# 8V54816A_SUPPLY.net
KiCad netlist of a schematic drawn in Altium Designer
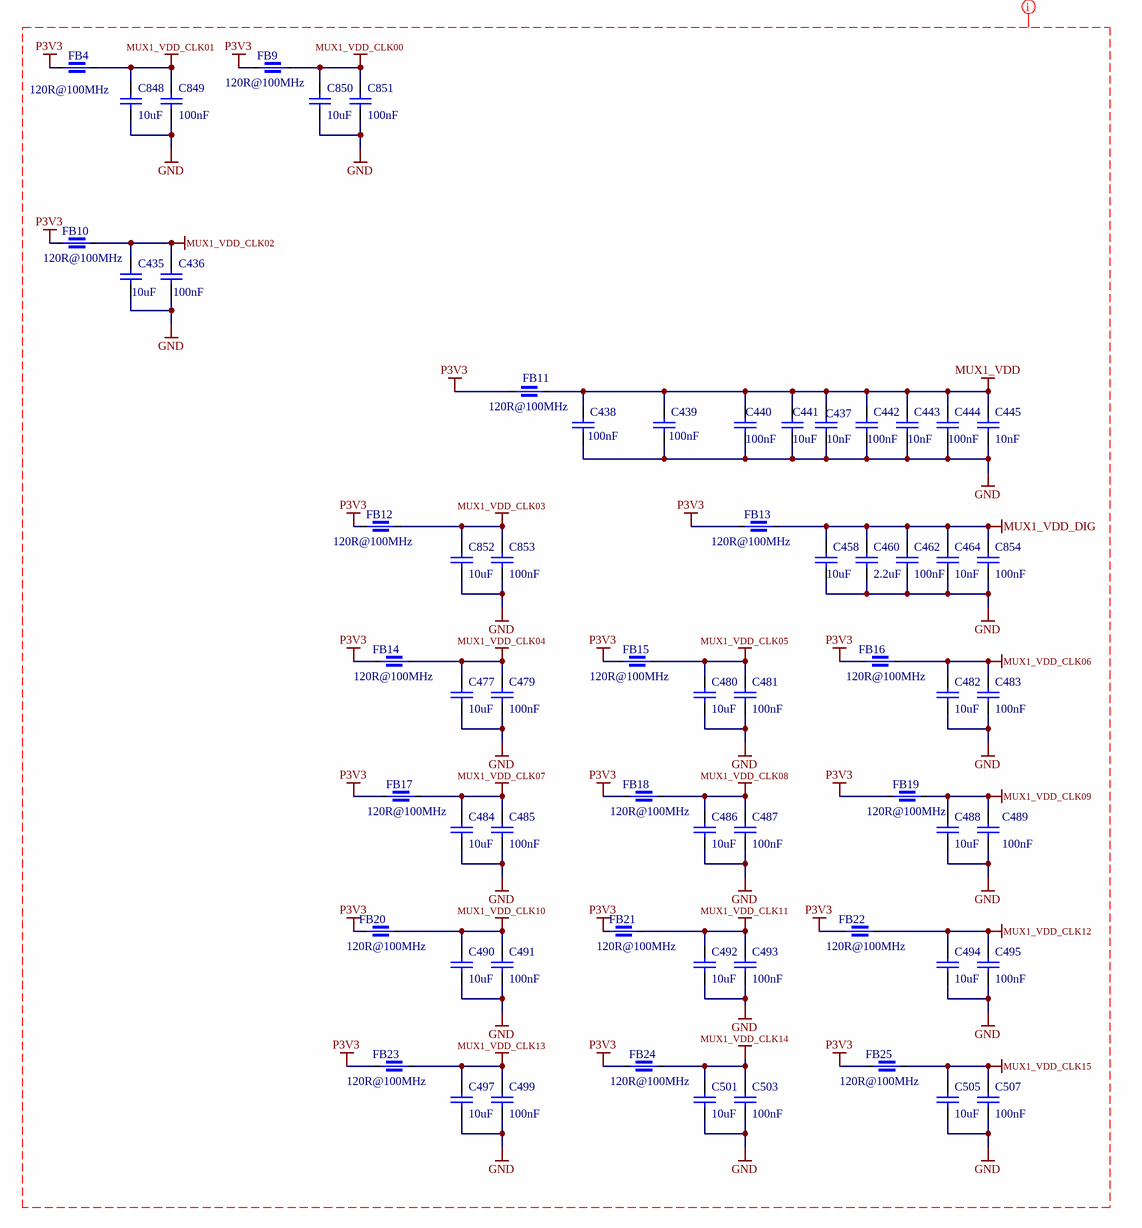
[diagram p0: 8V54816A_SUPPLY.SchDoc]

(export (version "E")
  (design (tool "Eeschema 10.0.6"))
  (components
    (comp (ref "C435")
      (value "10uF")
      (footprint "CAPC1608X87N")
      (description "Non-polarised capacitor")
      (fields
        (field (name "MANUFACTURER PART NUMBER") "CC0603_10uF_6.3V_20%_X5R")
        (field (name "MANUFACTURER") "GENERIC")
        (field (name "AUTHOR") "CERN DEM JLC")
      )
      (libsource (lib "Capacitors") (part "Capacitor - non polarized"))
    )
    (comp (ref "C436")
      (value "100nF")
      (footprint "CAPC0603X33N")
      (description "Non-polarised capacitor")
      (fields
        (field (name "MANUFACTURER PART NUMBER") "CC0201_100NF_6.3V_10%_X5R")
        (field (name "MANUFACTURER") "GENERIC")
        (field (name "AUTHOR") "CERN DEM JLC")
      )
      (libsource (lib "Capacitors") (part "Capacitor - non polarized"))
    )
    (comp (ref "C437")
      (value "10nF")
      (footprint "CAPC0603X33N")
      (description "Non-polarised capacitor")
      (fields
        (field (name "MANUFACTURER PART NUMBER") "CC0201_10NF_10V_10%_X5R")
        (field (name "MANUFACTURER") "GENERIC")
        (field (name "AUTHOR") "CERN DEM JLC")
      )
      (libsource (lib "Capacitors") (part "Capacitor - non polarized"))
    )
    (comp (ref "C438")
      (value "100nF")
      (footprint "CAPC0603X33N")
      (description "Non-polarised capacitor")
      (fields
        (field (name "MANUFACTURER PART NUMBER") "CC0201_100NF_6.3V_10%_X5R")
        (field (name "MANUFACTURER") "GENERIC")
        (field (name "AUTHOR") "CERN DEM JLC")
      )
      (libsource (lib "Capacitors") (part "Capacitor - non polarized"))
    )
    (comp (ref "C439")
      (value "100nF")
      (footprint "CAPC0603X33N")
      (description "Non-polarised capacitor")
      (fields
        (field (name "MANUFACTURER PART NUMBER") "CC0201_100NF_6.3V_10%_X5R")
        (field (name "MANUFACTURER") "GENERIC")
        (field (name "AUTHOR") "CERN DEM JLC")
      )
      (libsource (lib "Capacitors") (part "Capacitor - non polarized"))
    )
    (comp (ref "C440")
      (value "100nF")
      (footprint "CAPC0603X33N")
      (description "Non-polarised capacitor")
      (fields
        (field (name "MANUFACTURER PART NUMBER") "CC0201_100NF_6.3V_10%_X5R")
        (field (name "MANUFACTURER") "GENERIC")
        (field (name "AUTHOR") "CERN DEM JLC")
      )
      (libsource (lib "Capacitors") (part "Capacitor - non polarized"))
    )
    (comp (ref "C441")
      (value "10uF")
      (footprint "CAPC1608X87N")
      (description "Non-polarised capacitor")
      (fields
        (field (name "MANUFACTURER PART NUMBER") "CC0603_10uF_6.3V_20%_X5R")
        (field (name "MANUFACTURER") "GENERIC")
        (field (name "AUTHOR") "CERN DEM JLC")
      )
      (libsource (lib "Capacitors") (part "Capacitor - non polarized"))
    )
    (comp (ref "C442")
      (value "100nF")
      (footprint "CAPC0603X33N")
      (description "Non-polarised capacitor")
      (fields
        (field (name "MANUFACTURER PART NUMBER") "CC0201_100NF_6.3V_10%_X5R")
        (field (name "MANUFACTURER") "GENERIC")
        (field (name "AUTHOR") "CERN DEM JLC")
      )
      (libsource (lib "Capacitors") (part "Capacitor - non polarized"))
    )
    (comp (ref "C443")
      (value "10nF")
      (footprint "CAPC0603X33N")
      (description "Non-polarised capacitor")
      (fields
        (field (name "MANUFACTURER PART NUMBER") "CC0201_10NF_10V_10%_X5R")
        (field (name "MANUFACTURER") "GENERIC")
        (field (name "AUTHOR") "CERN DEM JLC")
      )
      (libsource (lib "Capacitors") (part "Capacitor - non polarized"))
    )
    (comp (ref "C444")
      (value "100nF")
      (footprint "CAPC0603X33N")
      (description "Non-polarised capacitor")
      (fields
        (field (name "MANUFACTURER PART NUMBER") "CC0201_100NF_6.3V_10%_X5R")
        (field (name "MANUFACTURER") "GENERIC")
        (field (name "AUTHOR") "CERN DEM JLC")
      )
      (libsource (lib "Capacitors") (part "Capacitor - non polarized"))
    )
    (comp (ref "C445")
      (value "10nF")
      (footprint "CAPC0603X33N")
      (description "Non-polarised capacitor")
      (fields
        (field (name "MANUFACTURER PART NUMBER") "CC0201_10NF_10V_10%_X5R")
        (field (name "MANUFACTURER") "GENERIC")
        (field (name "AUTHOR") "CERN DEM JLC")
      )
      (libsource (lib "Capacitors") (part "Capacitor - non polarized"))
    )
    (comp (ref "C458")
      (value "10uF")
      (footprint "CAPC1608X87N")
      (description "Non-polarised capacitor")
      (fields
        (field (name "MANUFACTURER PART NUMBER") "CC0603_10uF_6.3V_20%_X5R")
        (field (name "MANUFACTURER") "GENERIC")
        (field (name "AUTHOR") "CERN DEM JLC")
      )
      (libsource (lib "Capacitors") (part "Capacitor - non polarized"))
    )
    (comp (ref "C460")
      (value "2.2uF")
      (footprint "CAPC1005X55N")
      (description "Non-polarised capacitor")
      (fields
        (field (name "MANUFACTURER PART NUMBER") "CC0402_2.2UF_6.3V_10%_X5R")
        (field (name "MANUFACTURER") "GENERIC")
        (field (name "AUTHOR") "CERN DEM JMW")
      )
      (libsource (lib "Capacitors") (part "Capacitor - non polarized"))
    )
    (comp (ref "C462")
      (value "100nF")
      (footprint "CAPC0603X33N")
      (description "Non-polarised capacitor")
      (fields
        (field (name "MANUFACTURER PART NUMBER") "CC0201_100NF_6.3V_10%_X5R")
        (field (name "MANUFACTURER") "GENERIC")
        (field (name "AUTHOR") "CERN DEM JLC")
      )
      (libsource (lib "Capacitors") (part "Capacitor - non polarized"))
    )
    (comp (ref "C464")
      (value "10nF")
      (footprint "CAPC0603X33N")
      (description "Non-polarised capacitor")
      (fields
        (field (name "MANUFACTURER PART NUMBER") "CC0201_10NF_10V_10%_X5R")
        (field (name "MANUFACTURER") "GENERIC")
        (field (name "AUTHOR") "CERN DEM JLC")
      )
      (libsource (lib "Capacitors") (part "Capacitor - non polarized"))
    )
    (comp (ref "C477")
      (value "10uF")
      (footprint "CAPC1608X87N")
      (description "Non-polarised capacitor")
      (fields
        (field (name "MANUFACTURER PART NUMBER") "CC0603_10uF_6.3V_20%_X5R")
        (field (name "MANUFACTURER") "GENERIC")
        (field (name "AUTHOR") "CERN DEM JLC")
      )
      (libsource (lib "Capacitors") (part "Capacitor - non polarized"))
    )
    (comp (ref "C479")
      (value "100nF")
      (footprint "CAPC0603X33N")
      (description "Non-polarised capacitor")
      (fields
        (field (name "MANUFACTURER PART NUMBER") "CC0201_100NF_6.3V_10%_X5R")
        (field (name "MANUFACTURER") "GENERIC")
        (field (name "AUTHOR") "CERN DEM JLC")
      )
      (libsource (lib "Capacitors") (part "Capacitor - non polarized"))
    )
    (comp (ref "C480")
      (value "10uF")
      (footprint "CAPC1608X87N")
      (description "Non-polarised capacitor")
      (fields
        (field (name "MANUFACTURER PART NUMBER") "CC0603_10uF_6.3V_20%_X5R")
        (field (name "MANUFACTURER") "GENERIC")
        (field (name "AUTHOR") "CERN DEM JLC")
      )
      (libsource (lib "Capacitors") (part "Capacitor - non polarized"))
    )
    (comp (ref "C481")
      (value "100nF")
      (footprint "CAPC0603X33N")
      (description "Non-polarised capacitor")
      (fields
        (field (name "MANUFACTURER PART NUMBER") "CC0201_100NF_6.3V_10%_X5R")
        (field (name "MANUFACTURER") "GENERIC")
        (field (name "AUTHOR") "CERN DEM JLC")
      )
      (libsource (lib "Capacitors") (part "Capacitor - non polarized"))
    )
    (comp (ref "C482")
      (value "10uF")
      (footprint "CAPC1608X87N")
      (description "Non-polarised capacitor")
      (fields
        (field (name "MANUFACTURER PART NUMBER") "CC0603_10uF_6.3V_20%_X5R")
        (field (name "MANUFACTURER") "GENERIC")
        (field (name "AUTHOR") "CERN DEM JLC")
      )
      (libsource (lib "Capacitors") (part "Capacitor - non polarized"))
    )
    (comp (ref "C483")
      (value "100nF")
      (footprint "CAPC0603X33N")
      (description "Non-polarised capacitor")
      (fields
        (field (name "MANUFACTURER PART NUMBER") "CC0201_100NF_6.3V_10%_X5R")
        (field (name "MANUFACTURER") "GENERIC")
        (field (name "AUTHOR") "CERN DEM JLC")
      )
      (libsource (lib "Capacitors") (part "Capacitor - non polarized"))
    )
    (comp (ref "C484")
      (value "10uF")
      (footprint "CAPC1608X87N")
      (description "Non-polarised capacitor")
      (fields
        (field (name "MANUFACTURER PART NUMBER") "CC0603_10uF_6.3V_20%_X5R")
        (field (name "MANUFACTURER") "GENERIC")
        (field (name "AUTHOR") "CERN DEM JLC")
      )
      (libsource (lib "Capacitors") (part "Capacitor - non polarized"))
    )
    (comp (ref "C485")
      (value "100nF")
      (footprint "CAPC0603X33N")
      (description "Non-polarised capacitor")
      (fields
        (field (name "MANUFACTURER PART NUMBER") "CC0201_100NF_6.3V_10%_X5R")
        (field (name "MANUFACTURER") "GENERIC")
        (field (name "AUTHOR") "CERN DEM JLC")
      )
      (libsource (lib "Capacitors") (part "Capacitor - non polarized"))
    )
    (comp (ref "C486")
      (value "10uF")
      (footprint "CAPC1608X87N")
      (description "Non-polarised capacitor")
      (fields
        (field (name "MANUFACTURER PART NUMBER") "CC0603_10uF_6.3V_20%_X5R")
        (field (name "MANUFACTURER") "GENERIC")
        (field (name "AUTHOR") "CERN DEM JLC")
      )
      (libsource (lib "Capacitors") (part "Capacitor - non polarized"))
    )
    (comp (ref "C487")
      (value "100nF")
      (footprint "CAPC0603X33N")
      (description "Non-polarised capacitor")
      (fields
        (field (name "MANUFACTURER PART NUMBER") "CC0201_100NF_6.3V_10%_X5R")
        (field (name "MANUFACTURER") "GENERIC")
        (field (name "AUTHOR") "CERN DEM JLC")
      )
      (libsource (lib "Capacitors") (part "Capacitor - non polarized"))
    )
    (comp (ref "C488")
      (value "10uF")
      (footprint "CAPC1608X87N")
      (description "Non-polarised capacitor")
      (fields
        (field (name "MANUFACTURER PART NUMBER") "CC0603_10uF_6.3V_20%_X5R")
        (field (name "MANUFACTURER") "GENERIC")
        (field (name "AUTHOR") "CERN DEM JLC")
      )
      (libsource (lib "Capacitors") (part "Capacitor - non polarized"))
    )
    (comp (ref "C489")
      (value "100nF")
      (footprint "CAPC0603X33N")
      (description "Non-polarised capacitor")
      (fields
        (field (name "MANUFACTURER PART NUMBER") "CC0201_100NF_6.3V_10%_X5R")
        (field (name "MANUFACTURER") "GENERIC")
        (field (name "AUTHOR") "CERN DEM JLC")
      )
      (libsource (lib "Capacitors") (part "Capacitor - non polarized"))
    )
    (comp (ref "C490")
      (value "10uF")
      (footprint "CAPC1608X87N")
      (description "Non-polarised capacitor")
      (fields
        (field (name "MANUFACTURER PART NUMBER") "CC0603_10uF_6.3V_20%_X5R")
        (field (name "MANUFACTURER") "GENERIC")
        (field (name "AUTHOR") "CERN DEM JLC")
      )
      (libsource (lib "Capacitors") (part "Capacitor - non polarized"))
    )
    (comp (ref "C491")
      (value "100nF")
      (footprint "CAPC0603X33N")
      (description "Non-polarised capacitor")
      (fields
        (field (name "MANUFACTURER PART NUMBER") "CC0201_100NF_6.3V_10%_X5R")
        (field (name "MANUFACTURER") "GENERIC")
        (field (name "AUTHOR") "CERN DEM JLC")
      )
      (libsource (lib "Capacitors") (part "Capacitor - non polarized"))
    )
    (comp (ref "C492")
      (value "10uF")
      (footprint "CAPC1608X87N")
      (description "Non-polarised capacitor")
      (fields
        (field (name "MANUFACTURER PART NUMBER") "CC0603_10uF_6.3V_20%_X5R")
        (field (name "MANUFACTURER") "GENERIC")
        (field (name "AUTHOR") "CERN DEM JLC")
      )
      (libsource (lib "Capacitors") (part "Capacitor - non polarized"))
    )
    (comp (ref "C493")
      (value "100nF")
      (footprint "CAPC0603X33N")
      (description "Non-polarised capacitor")
      (fields
        (field (name "MANUFACTURER PART NUMBER") "CC0201_100NF_6.3V_10%_X5R")
        (field (name "MANUFACTURER") "GENERIC")
        (field (name "AUTHOR") "CERN DEM JLC")
      )
      (libsource (lib "Capacitors") (part "Capacitor - non polarized"))
    )
    (comp (ref "C494")
      (value "10uF")
      (footprint "CAPC1608X87N")
      (description "Non-polarised capacitor")
      (fields
        (field (name "MANUFACTURER PART NUMBER") "CC0603_10uF_6.3V_20%_X5R")
        (field (name "MANUFACTURER") "GENERIC")
        (field (name "AUTHOR") "CERN DEM JLC")
      )
      (libsource (lib "Capacitors") (part "Capacitor - non polarized"))
    )
    (comp (ref "C495")
      (value "100nF")
      (footprint "CAPC0603X33N")
      (description "Non-polarised capacitor")
      (fields
        (field (name "MANUFACTURER PART NUMBER") "CC0201_100NF_6.3V_10%_X5R")
        (field (name "MANUFACTURER") "GENERIC")
        (field (name "AUTHOR") "CERN DEM JLC")
      )
      (libsource (lib "Capacitors") (part "Capacitor - non polarized"))
    )
    (comp (ref "C497")
      (value "10uF")
      (footprint "CAPC1608X87N")
      (description "Non-polarised capacitor")
      (fields
        (field (name "MANUFACTURER PART NUMBER") "CC0603_10uF_6.3V_20%_X5R")
        (field (name "MANUFACTURER") "GENERIC")
        (field (name "AUTHOR") "CERN DEM JLC")
      )
      (libsource (lib "Capacitors") (part "Capacitor - non polarized"))
    )
    (comp (ref "C499")
      (value "100nF")
      (footprint "CAPC0603X33N")
      (description "Non-polarised capacitor")
      (fields
        (field (name "MANUFACTURER PART NUMBER") "CC0201_100NF_6.3V_10%_X5R")
        (field (name "MANUFACTURER") "GENERIC")
        (field (name "AUTHOR") "CERN DEM JLC")
      )
      (libsource (lib "Capacitors") (part "Capacitor - non polarized"))
    )
    (comp (ref "C501")
      (value "10uF")
      (footprint "CAPC1608X87N")
      (description "Non-polarised capacitor")
      (fields
        (field (name "MANUFACTURER PART NUMBER") "CC0603_10uF_6.3V_20%_X5R")
        (field (name "MANUFACTURER") "GENERIC")
        (field (name "AUTHOR") "CERN DEM JLC")
      )
      (libsource (lib "Capacitors") (part "Capacitor - non polarized"))
    )
    (comp (ref "C503")
      (value "100nF")
      (footprint "CAPC0603X33N")
      (description "Non-polarised capacitor")
      (fields
        (field (name "MANUFACTURER PART NUMBER") "CC0201_100NF_6.3V_10%_X5R")
        (field (name "MANUFACTURER") "GENERIC")
        (field (name "AUTHOR") "CERN DEM JLC")
      )
      (libsource (lib "Capacitors") (part "Capacitor - non polarized"))
    )
    (comp (ref "C505")
      (value "10uF")
      (footprint "CAPC1608X87N")
      (description "Non-polarised capacitor")
      (fields
        (field (name "MANUFACTURER PART NUMBER") "CC0603_10uF_6.3V_20%_X5R")
        (field (name "MANUFACTURER") "GENERIC")
        (field (name "AUTHOR") "CERN DEM JLC")
      )
      (libsource (lib "Capacitors") (part "Capacitor - non polarized"))
    )
    (comp (ref "C507")
      (value "100nF")
      (footprint "CAPC0603X33N")
      (description "Non-polarised capacitor")
      (fields
        (field (name "MANUFACTURER PART NUMBER") "CC0201_100NF_6.3V_10%_X5R")
        (field (name "MANUFACTURER") "GENERIC")
        (field (name "AUTHOR") "CERN DEM JLC")
      )
      (libsource (lib "Capacitors") (part "Capacitor - non polarized"))
    )
    (comp (ref "C848")
      (value "10uF")
      (footprint "CAPC1608X87N")
      (description "Non-polarised capacitor")
      (fields
        (field (name "MANUFACTURER PART NUMBER") "CC0603_10uF_6.3V_20%_X5R")
        (field (name "MANUFACTURER") "GENERIC")
        (field (name "AUTHOR") "CERN DEM JLC")
      )
      (libsource (lib "Capacitors") (part "Capacitor - non polarized"))
    )
    (comp (ref "C849")
      (value "100nF")
      (footprint "CAPC0603X33N")
      (description "Non-polarised capacitor")
      (fields
        (field (name "MANUFACTURER PART NUMBER") "CC0201_100NF_6.3V_10%_X5R")
        (field (name "MANUFACTURER") "GENERIC")
        (field (name "AUTHOR") "CERN DEM JLC")
      )
      (libsource (lib "Capacitors") (part "Capacitor - non polarized"))
    )
    (comp (ref "C850")
      (value "10uF")
      (footprint "CAPC1608X87N")
      (description "Non-polarised capacitor")
      (fields
        (field (name "MANUFACTURER PART NUMBER") "CC0603_10uF_6.3V_20%_X5R")
        (field (name "MANUFACTURER") "GENERIC")
        (field (name "AUTHOR") "CERN DEM JLC")
      )
      (libsource (lib "Capacitors") (part "Capacitor - non polarized"))
    )
    (comp (ref "C851")
      (value "100nF")
      (footprint "CAPC0603X33N")
      (description "Non-polarised capacitor")
      (fields
        (field (name "MANUFACTURER PART NUMBER") "CC0201_100NF_6.3V_10%_X5R")
        (field (name "MANUFACTURER") "GENERIC")
        (field (name "AUTHOR") "CERN DEM JLC")
      )
      (libsource (lib "Capacitors") (part "Capacitor - non polarized"))
    )
    (comp (ref "C852")
      (value "10uF")
      (footprint "CAPC1608X87N")
      (description "Non-polarised capacitor")
      (fields
        (field (name "MANUFACTURER PART NUMBER") "CC0603_10uF_6.3V_20%_X5R")
        (field (name "MANUFACTURER") "GENERIC")
        (field (name "AUTHOR") "CERN DEM JLC")
      )
      (libsource (lib "Capacitors") (part "Capacitor - non polarized"))
    )
    (comp (ref "C853")
      (value "100nF")
      (footprint "CAPC0603X33N")
      (description "Non-polarised capacitor")
      (fields
        (field (name "MANUFACTURER PART NUMBER") "CC0201_100NF_6.3V_10%_X5R")
        (field (name "MANUFACTURER") "GENERIC")
        (field (name "AUTHOR") "CERN DEM JLC")
      )
      (libsource (lib "Capacitors") (part "Capacitor - non polarized"))
    )
    (comp (ref "C854")
      (value "100nF")
      (footprint "CAPC0603X33N")
      (description "Non-polarised capacitor")
      (fields
        (field (name "MANUFACTURER PART NUMBER") "CC0201_100NF_6.3V_10%_X5R")
        (field (name "MANUFACTURER") "GENERIC")
        (field (name "AUTHOR") "CERN DEM JLC")
      )
      (libsource (lib "Capacitors") (part "Capacitor - non polarized"))
    )
    (comp (ref "FB4")
      (value "120R@100MHz")
      (footprint "INDC1005X55N")
      (fields
        (field (name "MANUFACTURER PART NUMBER") "BLM15PX121SN1D")
        (field (name "MANUFACTURER") "MURATA")
        (field (name "PART NUMBER") "IND0402_MURATA_BLM15PX121SN1D")
        (field (name "AUTHOR") "CERN DEM JMW")
      )
      (libsource (lib "Inductors & Transformers") (part "Ferrite Bead"))
    )
    (comp (ref "FB9")
      (value "120R@100MHz")
      (footprint "INDC1005X55N")
      (fields
        (field (name "MANUFACTURER PART NUMBER") "BLM15PX121SN1D")
        (field (name "MANUFACTURER") "MURATA")
        (field (name "PART NUMBER") "IND0402_MURATA_BLM15PX121SN1D")
        (field (name "AUTHOR") "CERN DEM JMW")
      )
      (libsource (lib "Inductors & Transformers") (part "Ferrite Bead"))
    )
    (comp (ref "FB10")
      (value "120R@100MHz")
      (footprint "INDC1005X55N")
      (fields
        (field (name "MANUFACTURER PART NUMBER") "BLM15PX121SN1D")
        (field (name "MANUFACTURER") "MURATA")
        (field (name "PART NUMBER") "IND0402_MURATA_BLM15PX121SN1D")
        (field (name "AUTHOR") "CERN DEM JMW")
      )
      (libsource (lib "Inductors & Transformers") (part "Ferrite Bead"))
    )
    (comp (ref "FB11")
      (value "120R@100MHz")
      (footprint "INDC1005X55N")
      (fields
        (field (name "MANUFACTURER PART NUMBER") "BLM15PX121SN1D")
        (field (name "MANUFACTURER") "MURATA")
        (field (name "PART NUMBER") "IND0402_MURATA_BLM15PX121SN1D")
        (field (name "AUTHOR") "CERN DEM JMW")
      )
      (libsource (lib "Inductors & Transformers") (part "Ferrite Bead"))
    )
    (comp (ref "FB12")
      (value "120R@100MHz")
      (footprint "INDC1005X55N")
      (fields
        (field (name "MANUFACTURER PART NUMBER") "BLM15PX121SN1D")
        (field (name "MANUFACTURER") "MURATA")
        (field (name "PART NUMBER") "IND0402_MURATA_BLM15PX121SN1D")
        (field (name "AUTHOR") "CERN DEM JMW")
      )
      (libsource (lib "Inductors & Transformers") (part "Ferrite Bead"))
    )
    (comp (ref "FB13")
      (value "120R@100MHz")
      (footprint "INDC1005X55N")
      (fields
        (field (name "MANUFACTURER PART NUMBER") "BLM15PX121SN1D")
        (field (name "MANUFACTURER") "MURATA")
        (field (name "PART NUMBER") "IND0402_MURATA_BLM15PX121SN1D")
        (field (name "AUTHOR") "CERN DEM JMW")
      )
      (libsource (lib "Inductors & Transformers") (part "Ferrite Bead"))
    )
    (comp (ref "FB14")
      (value "120R@100MHz")
      (footprint "INDC1005X55N")
      (fields
        (field (name "MANUFACTURER PART NUMBER") "BLM15PX121SN1D")
        (field (name "MANUFACTURER") "MURATA")
        (field (name "PART NUMBER") "IND0402_MURATA_BLM15PX121SN1D")
        (field (name "AUTHOR") "CERN DEM JMW")
      )
      (libsource (lib "Inductors & Transformers") (part "Ferrite Bead"))
    )
    (comp (ref "FB15")
      (value "120R@100MHz")
      (footprint "INDC1005X55N")
      (fields
        (field (name "MANUFACTURER PART NUMBER") "BLM15PX121SN1D")
        (field (name "MANUFACTURER") "MURATA")
        (field (name "PART NUMBER") "IND0402_MURATA_BLM15PX121SN1D")
        (field (name "AUTHOR") "CERN DEM JMW")
      )
      (libsource (lib "Inductors & Transformers") (part "Ferrite Bead"))
    )
    (comp (ref "FB16")
      (value "120R@100MHz")
      (footprint "INDC1005X55N")
      (fields
        (field (name "MANUFACTURER PART NUMBER") "BLM15PX121SN1D")
        (field (name "MANUFACTURER") "MURATA")
        (field (name "PART NUMBER") "IND0402_MURATA_BLM15PX121SN1D")
        (field (name "AUTHOR") "CERN DEM JMW")
      )
      (libsource (lib "Inductors & Transformers") (part "Ferrite Bead"))
    )
    (comp (ref "FB17")
      (value "120R@100MHz")
      (footprint "INDC1005X55N")
      (fields
        (field (name "MANUFACTURER PART NUMBER") "BLM15PX121SN1D")
        (field (name "MANUFACTURER") "MURATA")
        (field (name "PART NUMBER") "IND0402_MURATA_BLM15PX121SN1D")
        (field (name "AUTHOR") "CERN DEM JMW")
      )
      (libsource (lib "Inductors & Transformers") (part "Ferrite Bead"))
    )
    (comp (ref "FB18")
      (value "120R@100MHz")
      (footprint "INDC1005X55N")
      (fields
        (field (name "MANUFACTURER PART NUMBER") "BLM15PX121SN1D")
        (field (name "MANUFACTURER") "MURATA")
        (field (name "PART NUMBER") "IND0402_MURATA_BLM15PX121SN1D")
        (field (name "AUTHOR") "CERN DEM JMW")
      )
      (libsource (lib "Inductors & Transformers") (part "Ferrite Bead"))
    )
    (comp (ref "FB19")
      (value "120R@100MHz")
      (footprint "INDC1005X55N")
      (fields
        (field (name "MANUFACTURER PART NUMBER") "BLM15PX121SN1D")
        (field (name "MANUFACTURER") "MURATA")
        (field (name "PART NUMBER") "IND0402_MURATA_BLM15PX121SN1D")
        (field (name "AUTHOR") "CERN DEM JMW")
      )
      (libsource (lib "Inductors & Transformers") (part "Ferrite Bead"))
    )
    (comp (ref "FB20")
      (value "120R@100MHz")
      (footprint "INDC1005X55N")
      (fields
        (field (name "MANUFACTURER PART NUMBER") "BLM15PX121SN1D")
        (field (name "MANUFACTURER") "MURATA")
        (field (name "PART NUMBER") "IND0402_MURATA_BLM15PX121SN1D")
        (field (name "AUTHOR") "CERN DEM JMW")
      )
      (libsource (lib "Inductors & Transformers") (part "Ferrite Bead"))
    )
    (comp (ref "FB21")
      (value "120R@100MHz")
      (footprint "INDC1005X55N")
      (fields
        (field (name "MANUFACTURER PART NUMBER") "BLM15PX121SN1D")
        (field (name "MANUFACTURER") "MURATA")
        (field (name "PART NUMBER") "IND0402_MURATA_BLM15PX121SN1D")
        (field (name "AUTHOR") "CERN DEM JMW")
      )
      (libsource (lib "Inductors & Transformers") (part "Ferrite Bead"))
    )
    (comp (ref "FB22")
      (value "120R@100MHz")
      (footprint "INDC1005X55N")
      (fields
        (field (name "MANUFACTURER PART NUMBER") "BLM15PX121SN1D")
        (field (name "MANUFACTURER") "MURATA")
        (field (name "PART NUMBER") "IND0402_MURATA_BLM15PX121SN1D")
        (field (name "AUTHOR") "CERN DEM JMW")
      )
      (libsource (lib "Inductors & Transformers") (part "Ferrite Bead"))
    )
    (comp (ref "FB23")
      (value "120R@100MHz")
      (footprint "INDC1005X55N")
      (fields
        (field (name "MANUFACTURER PART NUMBER") "BLM15PX121SN1D")
        (field (name "MANUFACTURER") "MURATA")
        (field (name "PART NUMBER") "IND0402_MURATA_BLM15PX121SN1D")
        (field (name "AUTHOR") "CERN DEM JMW")
      )
      (libsource (lib "Inductors & Transformers") (part "Ferrite Bead"))
    )
    (comp (ref "FB24")
      (value "120R@100MHz")
      (footprint "INDC1005X55N")
      (fields
        (field (name "MANUFACTURER PART NUMBER") "BLM15PX121SN1D")
        (field (name "MANUFACTURER") "MURATA")
        (field (name "PART NUMBER") "IND0402_MURATA_BLM15PX121SN1D")
        (field (name "AUTHOR") "CERN DEM JMW")
      )
      (libsource (lib "Inductors & Transformers") (part "Ferrite Bead"))
    )
    (comp (ref "FB25")
      (value "120R@100MHz")
      (footprint "INDC1005X55N")
      (fields
        (field (name "MANUFACTURER PART NUMBER") "BLM15PX121SN1D")
        (field (name "MANUFACTURER") "MURATA")
        (field (name "PART NUMBER") "IND0402_MURATA_BLM15PX121SN1D")
        (field (name "AUTHOR") "CERN DEM JMW")
      )
      (libsource (lib "Inductors & Transformers") (part "Ferrite Bead"))
    )
  )
  (nets
    (net (code "1") (name "GND") (class "Default")
      (node (ref "C435") (pin "1") (pinfunction "1_1") (pintype "passive"))
      (node (ref "C436") (pin "1") (pinfunction "1_1") (pintype "passive"))
      (node (ref "C437") (pin "1") (pinfunction "1_1") (pintype "passive"))
      (node (ref "C438") (pin "1") (pinfunction "1_1") (pintype "passive"))
      (node (ref "C439") (pin "1") (pinfunction "1_1") (pintype "passive"))
      (node (ref "C440") (pin "1") (pinfunction "1_1") (pintype "passive"))
      (node (ref "C441") (pin "1") (pinfunction "1_1") (pintype "passive"))
      (node (ref "C442") (pin "1") (pinfunction "1_1") (pintype "passive"))
      (node (ref "C443") (pin "1") (pinfunction "1_1") (pintype "passive"))
      (node (ref "C444") (pin "1") (pinfunction "1_1") (pintype "passive"))
      (node (ref "C445") (pin "1") (pinfunction "1_1") (pintype "passive"))
      (node (ref "C458") (pin "1") (pinfunction "1_1") (pintype "passive"))
      (node (ref "C460") (pin "1") (pinfunction "1_1") (pintype "passive"))
      (node (ref "C462") (pin "1") (pinfunction "1_1") (pintype "passive"))
      (node (ref "C464") (pin "1") (pinfunction "1_1") (pintype "passive"))
      (node (ref "C477") (pin "1") (pinfunction "1_1") (pintype "passive"))
      (node (ref "C479") (pin "1") (pinfunction "1_1") (pintype "passive"))
      (node (ref "C480") (pin "1") (pinfunction "1_1") (pintype "passive"))
      (node (ref "C481") (pin "1") (pinfunction "1_1") (pintype "passive"))
      (node (ref "C482") (pin "1") (pinfunction "1_1") (pintype "passive"))
      (node (ref "C483") (pin "1") (pinfunction "1_1") (pintype "passive"))
      (node (ref "C484") (pin "1") (pinfunction "1_1") (pintype "passive"))
      (node (ref "C485") (pin "1") (pinfunction "1_1") (pintype "passive"))
      (node (ref "C486") (pin "1") (pinfunction "1_1") (pintype "passive"))
      (node (ref "C487") (pin "1") (pinfunction "1_1") (pintype "passive"))
      (node (ref "C488") (pin "1") (pinfunction "1_1") (pintype "passive"))
      (node (ref "C489") (pin "1") (pinfunction "1_1") (pintype "passive"))
      (node (ref "C490") (pin "1") (pinfunction "1_1") (pintype "passive"))
      (node (ref "C491") (pin "1") (pinfunction "1_1") (pintype "passive"))
      (node (ref "C492") (pin "1") (pinfunction "1_1") (pintype "passive"))
      (node (ref "C493") (pin "1") (pinfunction "1_1") (pintype "passive"))
      (node (ref "C494") (pin "1") (pinfunction "1_1") (pintype "passive"))
      (node (ref "C495") (pin "1") (pinfunction "1_1") (pintype "passive"))
      (node (ref "C497") (pin "1") (pinfunction "1_1") (pintype "passive"))
      (node (ref "C499") (pin "1") (pinfunction "1_1") (pintype "passive"))
      (node (ref "C501") (pin "1") (pinfunction "1_1") (pintype "passive"))
      (node (ref "C503") (pin "1") (pinfunction "1_1") (pintype "passive"))
      (node (ref "C505") (pin "1") (pinfunction "1_1") (pintype "passive"))
      (node (ref "C507") (pin "1") (pinfunction "1_1") (pintype "passive"))
      (node (ref "C848") (pin "1") (pinfunction "1_1") (pintype "passive"))
      (node (ref "C849") (pin "1") (pinfunction "1_1") (pintype "passive"))
      (node (ref "C850") (pin "1") (pinfunction "1_1") (pintype "passive"))
      (node (ref "C851") (pin "1") (pinfunction "1_1") (pintype "passive"))
      (node (ref "C852") (pin "1") (pinfunction "1_1") (pintype "passive"))
      (node (ref "C853") (pin "1") (pinfunction "1_1") (pintype "passive"))
      (node (ref "C854") (pin "1") (pinfunction "1_1") (pintype "passive"))
    )
    (net (code "2") (name "MUX1_VDD") (class "Default")
      (node (ref "C437") (pin "2") (pinfunction "2_2") (pintype "passive"))
      (node (ref "C438") (pin "2") (pinfunction "2_2") (pintype "passive"))
      (node (ref "C439") (pin "2") (pinfunction "2_2") (pintype "passive"))
      (node (ref "C440") (pin "2") (pinfunction "2_2") (pintype "passive"))
      (node (ref "C441") (pin "2") (pinfunction "2_2") (pintype "passive"))
      (node (ref "C442") (pin "2") (pinfunction "2_2") (pintype "passive"))
      (node (ref "C443") (pin "2") (pinfunction "2_2") (pintype "passive"))
      (node (ref "C444") (pin "2") (pinfunction "2_2") (pintype "passive"))
      (node (ref "C445") (pin "2") (pinfunction "2_2") (pintype "passive"))
      (node (ref "FB11") (pin "1") (pinfunction "1_1") (pintype "passive"))
    )
    (net (code "3") (name "MUX1_VDD_CLK00") (class "Default")
      (node (ref "C850") (pin "2") (pinfunction "2_2") (pintype "passive"))
      (node (ref "C851") (pin "2") (pinfunction "2_2") (pintype "passive"))
      (node (ref "FB9") (pin "1") (pinfunction "1_1") (pintype "passive"))
    )
    (net (code "4") (name "MUX1_VDD_CLK01") (class "Default")
      (node (ref "C848") (pin "2") (pinfunction "2_2") (pintype "passive"))
      (node (ref "C849") (pin "2") (pinfunction "2_2") (pintype "passive"))
      (node (ref "FB4") (pin "1") (pinfunction "1_1") (pintype "passive"))
    )
    (net (code "5") (name "MUX1_VDD_CLK02") (class "Default")
      (node (ref "C435") (pin "2") (pinfunction "2_2") (pintype "passive"))
      (node (ref "C436") (pin "2") (pinfunction "2_2") (pintype "passive"))
      (node (ref "FB10") (pin "1") (pinfunction "1_1") (pintype "passive"))
    )
    (net (code "6") (name "MUX1_VDD_CLK03") (class "Default")
      (node (ref "C852") (pin "2") (pinfunction "2_2") (pintype "passive"))
      (node (ref "C853") (pin "2") (pinfunction "2_2") (pintype "passive"))
      (node (ref "FB12") (pin "1") (pinfunction "1_1") (pintype "passive"))
    )
    (net (code "7") (name "MUX1_VDD_CLK04") (class "Default")
      (node (ref "C477") (pin "2") (pinfunction "2_2") (pintype "passive"))
      (node (ref "C479") (pin "2") (pinfunction "2_2") (pintype "passive"))
      (node (ref "FB14") (pin "1") (pinfunction "1_1") (pintype "passive"))
    )
    (net (code "8") (name "MUX1_VDD_CLK05") (class "Default")
      (node (ref "C480") (pin "2") (pinfunction "2_2") (pintype "passive"))
      (node (ref "C481") (pin "2") (pinfunction "2_2") (pintype "passive"))
      (node (ref "FB15") (pin "1") (pinfunction "1_1") (pintype "passive"))
    )
    (net (code "9") (name "MUX1_VDD_CLK06") (class "Default")
      (node (ref "C482") (pin "2") (pinfunction "2_2") (pintype "passive"))
      (node (ref "C483") (pin "2") (pinfunction "2_2") (pintype "passive"))
      (node (ref "FB16") (pin "1") (pinfunction "1_1") (pintype "passive"))
    )
    (net (code "10") (name "MUX1_VDD_CLK07") (class "Default")
      (node (ref "C484") (pin "2") (pinfunction "2_2") (pintype "passive"))
      (node (ref "C485") (pin "2") (pinfunction "2_2") (pintype "passive"))
      (node (ref "FB17") (pin "1") (pinfunction "1_1") (pintype "passive"))
    )
    (net (code "11") (name "MUX1_VDD_CLK08") (class "Default")
      (node (ref "C486") (pin "2") (pinfunction "2_2") (pintype "passive"))
      (node (ref "C487") (pin "2") (pinfunction "2_2") (pintype "passive"))
      (node (ref "FB18") (pin "1") (pinfunction "1_1") (pintype "passive"))
    )
    (net (code "12") (name "MUX1_VDD_CLK09") (class "Default")
      (node (ref "C488") (pin "2") (pinfunction "2_2") (pintype "passive"))
      (node (ref "C489") (pin "2") (pinfunction "2_2") (pintype "passive"))
      (node (ref "FB19") (pin "1") (pinfunction "1_1") (pintype "passive"))
    )
    (net (code "13") (name "MUX1_VDD_CLK10") (class "Default")
      (node (ref "C490") (pin "2") (pinfunction "2_2") (pintype "passive"))
      (node (ref "C491") (pin "2") (pinfunction "2_2") (pintype "passive"))
      (node (ref "FB20") (pin "1") (pinfunction "1_1") (pintype "passive"))
    )
    (net (code "14") (name "MUX1_VDD_CLK11") (class "Default")
      (node (ref "C492") (pin "2") (pinfunction "2_2") (pintype "passive"))
      (node (ref "C493") (pin "2") (pinfunction "2_2") (pintype "passive"))
      (node (ref "FB21") (pin "1") (pinfunction "1_1") (pintype "passive"))
    )
    (net (code "15") (name "MUX1_VDD_CLK12") (class "Default")
      (node (ref "C494") (pin "2") (pinfunction "2_2") (pintype "passive"))
      (node (ref "C495") (pin "2") (pinfunction "2_2") (pintype "passive"))
      (node (ref "FB22") (pin "1") (pinfunction "1_1") (pintype "passive"))
    )
    (net (code "16") (name "MUX1_VDD_CLK13") (class "Default")
      (node (ref "C497") (pin "2") (pinfunction "2_2") (pintype "passive"))
      (node (ref "C499") (pin "2") (pinfunction "2_2") (pintype "passive"))
      (node (ref "FB23") (pin "1") (pinfunction "1_1") (pintype "passive"))
    )
    (net (code "17") (name "MUX1_VDD_CLK14") (class "Default")
      (node (ref "C501") (pin "2") (pinfunction "2_2") (pintype "passive"))
      (node (ref "C503") (pin "2") (pinfunction "2_2") (pintype "passive"))
      (node (ref "FB24") (pin "1") (pinfunction "1_1") (pintype "passive"))
    )
    (net (code "18") (name "MUX1_VDD_CLK15") (class "Default")
      (node (ref "C505") (pin "2") (pinfunction "2_2") (pintype "passive"))
      (node (ref "C507") (pin "2") (pinfunction "2_2") (pintype "passive"))
      (node (ref "FB25") (pin "1") (pinfunction "1_1") (pintype "passive"))
    )
    (net (code "19") (name "MUX1_VDD_DIG") (class "Default")
      (node (ref "C458") (pin "2") (pinfunction "2_2") (pintype "passive"))
      (node (ref "C460") (pin "2") (pinfunction "2_2") (pintype "passive"))
      (node (ref "C462") (pin "2") (pinfunction "2_2") (pintype "passive"))
      (node (ref "C464") (pin "2") (pinfunction "2_2") (pintype "passive"))
      (node (ref "C854") (pin "2") (pinfunction "2_2") (pintype "passive"))
      (node (ref "FB13") (pin "1") (pinfunction "1_1") (pintype "passive"))
    )
    (net (code "20") (name "P3V3") (class "Default")
      (node (ref "FB10") (pin "2") (pinfunction "2_2") (pintype "passive"))
      (node (ref "FB11") (pin "2") (pinfunction "2_2") (pintype "passive"))
      (node (ref "FB12") (pin "2") (pinfunction "2_2") (pintype "passive"))
      (node (ref "FB13") (pin "2") (pinfunction "2_2") (pintype "passive"))
      (node (ref "FB14") (pin "2") (pinfunction "2_2") (pintype "passive"))
      (node (ref "FB15") (pin "2") (pinfunction "2_2") (pintype "passive"))
      (node (ref "FB16") (pin "2") (pinfunction "2_2") (pintype "passive"))
      (node (ref "FB17") (pin "2") (pinfunction "2_2") (pintype "passive"))
      (node (ref "FB18") (pin "2") (pinfunction "2_2") (pintype "passive"))
      (node (ref "FB19") (pin "2") (pinfunction "2_2") (pintype "passive"))
      (node (ref "FB20") (pin "2") (pinfunction "2_2") (pintype "passive"))
      (node (ref "FB21") (pin "2") (pinfunction "2_2") (pintype "passive"))
      (node (ref "FB22") (pin "2") (pinfunction "2_2") (pintype "passive"))
      (node (ref "FB23") (pin "2") (pinfunction "2_2") (pintype "passive"))
      (node (ref "FB24") (pin "2") (pinfunction "2_2") (pintype "passive"))
      (node (ref "FB25") (pin "2") (pinfunction "2_2") (pintype "passive"))
      (node (ref "FB4") (pin "2") (pinfunction "2_2") (pintype "passive"))
      (node (ref "FB9") (pin "2") (pinfunction "2_2") (pintype "passive"))
    )
  )
)
